# Thetis_RevF4_SCH.net
KiCad netlist of a schematic drawn in EAGLE
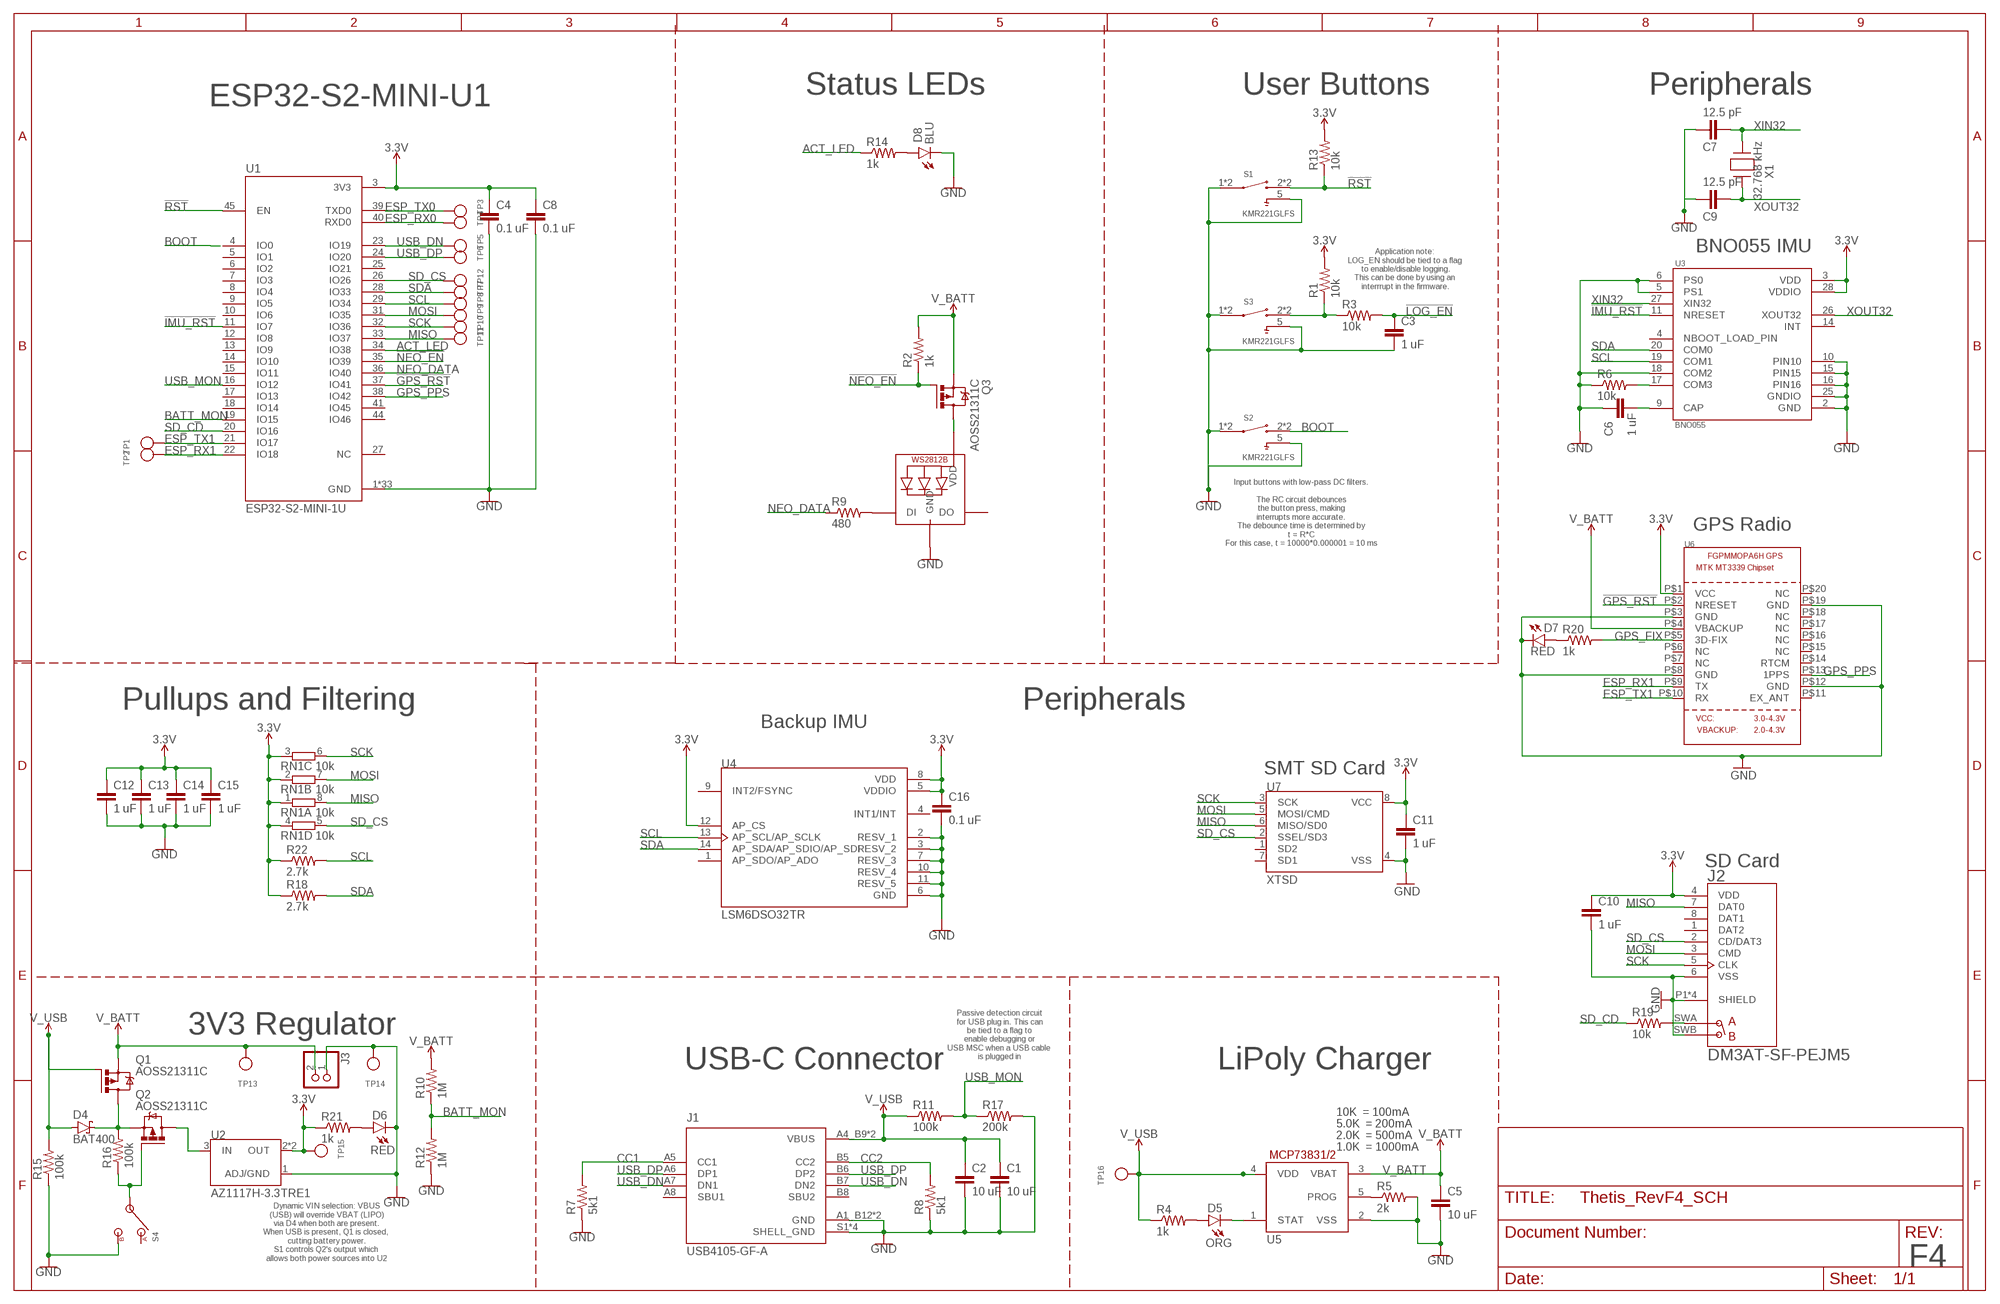
[diagram p0: schematic, sheet 1]

(export (version "E")
  (design (tool "Eeschema 10.0.6"))
  (components
    (comp (ref "C1")
      (value "10 uF")
      (footprint "eagle-import:C0603")
      (libsource (lib "eagle-import") (part "C-EUC0603"))
    )
    (comp (ref "C2")
      (value "10 uF")
      (footprint "eagle-import:C0603")
      (libsource (lib "eagle-import") (part "C-EUC0603"))
    )
    (comp (ref "C3")
      (value "1 uF")
      (footprint "eagle-import:C0603")
      (libsource (lib "eagle-import") (part "C-EUC0603"))
    )
    (comp (ref "C4")
      (value "0.1 uF")
      (footprint "eagle-import:C0603")
      (libsource (lib "eagle-import") (part "C-EUC0603"))
    )
    (comp (ref "C5")
      (value "10 uF")
      (footprint "eagle-import:C0603")
      (libsource (lib "eagle-import") (part "C-EUC0603"))
    )
    (comp (ref "C6")
      (value "1 uF")
      (footprint "eagle-import:C0603")
      (libsource (lib "eagle-import") (part "C-EUC0603"))
    )
    (comp (ref "C7")
      (value "12.5 pF")
      (footprint "eagle-import:C0603")
      (libsource (lib "eagle-import") (part "C-EUC0603"))
    )
    (comp (ref "C8")
      (value "0.1 uF")
      (footprint "eagle-import:C0603")
      (libsource (lib "eagle-import") (part "C-EUC0603"))
    )
    (comp (ref "C9")
      (value "12.5 pF")
      (footprint "eagle-import:C0603")
      (libsource (lib "eagle-import") (part "C-EUC0603"))
    )
    (comp (ref "C10")
      (value "1 uF")
      (footprint "eagle-import:C0603")
      (libsource (lib "eagle-import") (part "C-EUC0603"))
    )
    (comp (ref "C11")
      (value "1 uF")
      (footprint "eagle-import:C0603")
      (libsource (lib "eagle-import") (part "C-EUC0603"))
    )
    (comp (ref "C12")
      (value "1 uF")
      (footprint "eagle-import:C0603")
      (libsource (lib "eagle-import") (part "C-EUC0603"))
    )
    (comp (ref "C13")
      (value "1 uF")
      (footprint "eagle-import:C0603")
      (libsource (lib "eagle-import") (part "C-EUC0603"))
    )
    (comp (ref "C14")
      (value "1 uF")
      (footprint "eagle-import:C0603")
      (libsource (lib "eagle-import") (part "C-EUC0603"))
    )
    (comp (ref "C15")
      (value "1 uF")
      (footprint "eagle-import:C0603")
      (libsource (lib "eagle-import") (part "C-EUC0603"))
    )
    (comp (ref "C16")
      (value "0.1 uF")
      (footprint "eagle-import:C0603")
      (libsource (lib "eagle-import") (part "C-EUC0603"))
    )
    (comp (ref "D4")
      (value "BAT400")
      (footprint "eagle-import:SOT23")
      (libsource (lib "eagle-import") (part "BAS40"))
    )
    (comp (ref "D5")
      (value "ORG")
      (footprint "eagle-import:LEDC1608X65N")
      (libsource (lib "eagle-import") (part "CHIP-ROUND-G_0603"))
    )
    (comp (ref "D6")
      (value "RED")
      (footprint "eagle-import:LEDC1608X65N")
      (libsource (lib "eagle-import") (part "CHIP-ROUND-G_0603"))
    )
    (comp (ref "D7")
      (value "RED")
      (footprint "eagle-import:LEDC1608X35N")
      (libsource (lib "eagle-import") (part "CHIP-FLAT-Y_0603-0.35MM"))
    )
    (comp (ref "D8")
      (value "BLU")
      (footprint "eagle-import:LEDC1608X65N")
      (libsource (lib "eagle-import") (part "CHIP-ROUND-G_0603"))
    )
    (comp (ref "J1")
      (value "USB4105-GF-A")
      (footprint "eagle-import:GCT_USB4105-GF-A")
      (fields (field (name "MF") "GCT"))
      (libsource (lib "eagle-import") (part "USB4105-GF-A"))
    )
    (comp (ref "J2")
      (value "DM3AT-SF-PEJM5")
      (footprint "eagle-import:HRS_DM3AT-SF-PEJM5")
      (fields (field (name "MF") "Hirose"))
      (libsource (lib "eagle-import") (part "DM3AT-SF-PEJM5"))
    )
    (comp (ref "J3")
      (value "JST_2PIN")
      (footprint "eagle-import:JSTPH2")
      (libsource (lib "eagle-import") (part "JST_2PIN"))
    )
    (comp (ref "LED1")
      (value "WS2812B3535")
      (footprint "eagle-import:LED3535")
      (libsource (lib "eagle-import") (part "WS2812B3535"))
    )
    (comp (ref "Q1")
      (value "AOSS21311C")
      (footprint "eagle-import:SOT23")
      (fields (field (name "MANUFACTURER") "ON Semiconductor") (field (name "MPN") "BSS84"))
      (libsource (lib "eagle-import") (part "PMOSFET_BSS84"))
    )
    (comp (ref "Q2")
      (value "AOSS21311C")
      (footprint "eagle-import:SOT23")
      (fields (field (name "MANUFACTURER") "ON Semiconductor") (field (name "MPN") "BSS84"))
      (libsource (lib "eagle-import") (part "PMOSFET_BSS84"))
    )
    (comp (ref "Q3")
      (value "AOSS21311C")
      (footprint "eagle-import:SOT23")
      (fields (field (name "MANUFACTURER") "ON Semiconductor") (field (name "MPN") "BSS84"))
      (libsource (lib "eagle-import") (part "PMOSFET_BSS84"))
    )
    (comp (ref "R1")
      (value "10k")
      (footprint "eagle-import:R0603")
      (libsource (lib "eagle-import") (part "R-US_R0603"))
    )
    (comp (ref "R2")
      (value "1k")
      (footprint "eagle-import:R0603")
      (libsource (lib "eagle-import") (part "R-US_R0603"))
    )
    (comp (ref "R3")
      (value "10k")
      (footprint "eagle-import:R0603")
      (libsource (lib "eagle-import") (part "R-US_R0603"))
    )
    (comp (ref "R4")
      (value "1k")
      (footprint "eagle-import:R0603")
      (libsource (lib "eagle-import") (part "R-US_R0603"))
    )
    (comp (ref "R5")
      (value "2k")
      (footprint "eagle-import:R0603")
      (libsource (lib "eagle-import") (part "R-US_R0603"))
    )
    (comp (ref "R6")
      (value "10k")
      (footprint "eagle-import:R0603")
      (libsource (lib "eagle-import") (part "R-US_R0603"))
    )
    (comp (ref "R7")
      (value "5k1")
      (footprint "eagle-import:R0603")
      (libsource (lib "eagle-import") (part "R-US_R0603"))
    )
    (comp (ref "R8")
      (value "5k1")
      (footprint "eagle-import:R0603")
      (libsource (lib "eagle-import") (part "R-US_R0603"))
    )
    (comp (ref "R9")
      (value "480")
      (footprint "eagle-import:R0603")
      (libsource (lib "eagle-import") (part "R-US_R0603"))
    )
    (comp (ref "R10")
      (value "1M")
      (footprint "eagle-import:R0603")
      (libsource (lib "eagle-import") (part "R-US_R0603"))
    )
    (comp (ref "R11")
      (value "100k")
      (footprint "eagle-import:R0603")
      (libsource (lib "eagle-import") (part "R-US_R0603"))
    )
    (comp (ref "R12")
      (value "1M")
      (footprint "eagle-import:R0603")
      (libsource (lib "eagle-import") (part "R-US_R0603"))
    )
    (comp (ref "R13")
      (value "10k")
      (footprint "eagle-import:R0603")
      (libsource (lib "eagle-import") (part "R-US_R0603"))
    )
    (comp (ref "R14")
      (value "1k")
      (footprint "eagle-import:R0603")
      (libsource (lib "eagle-import") (part "R-US_R0603"))
    )
    (comp (ref "R15")
      (value "100k")
      (footprint "eagle-import:R0603")
      (libsource (lib "eagle-import") (part "R-US_R0603"))
    )
    (comp (ref "R16")
      (value "100k")
      (footprint "eagle-import:R0603")
      (libsource (lib "eagle-import") (part "R-US_R0603"))
    )
    (comp (ref "R17")
      (value "200k")
      (footprint "eagle-import:R0603")
      (libsource (lib "eagle-import") (part "R-US_R0603"))
    )
    (comp (ref "R18")
      (value "2.7k")
      (footprint "eagle-import:R0603")
      (libsource (lib "eagle-import") (part "R-US_R0603"))
    )
    (comp (ref "R19")
      (value "10k")
      (footprint "eagle-import:R0603")
      (libsource (lib "eagle-import") (part "R-US_R0603"))
    )
    (comp (ref "R20")
      (value "1k")
      (footprint "eagle-import:R0603")
      (libsource (lib "eagle-import") (part "R-US_R0603"))
    )
    (comp (ref "R21")
      (value "1k")
      (footprint "eagle-import:R0603")
      (libsource (lib "eagle-import") (part "R-US_R0603"))
    )
    (comp (ref "R22")
      (value "2.7k")
      (footprint "eagle-import:R0603")
      (libsource (lib "eagle-import") (part "R-US_R0603"))
    )
    (comp (ref "RN1")
      (value "10k")
      (footprint "eagle-import:EXBN8V")
      (libsource (lib "eagle-import") (part "4R-NEXBN8V"))
    )
    (comp (ref "S1")
      (value "KMR221GLFS")
      (footprint "eagle-import:SW_KMR221GLFS")
      (fields (field (name "MANUFACTURER") "CnK"))
      (libsource (lib "eagle-import") (part "KMR221GLFS"))
    )
    (comp (ref "S2")
      (value "KMR221GLFS")
      (footprint "eagle-import:SW_KMR221GLFS")
      (fields (field (name "MANUFACTURER") "CnK"))
      (libsource (lib "eagle-import") (part "KMR221GLFS"))
    )
    (comp (ref "S3")
      (value "KMR221GLFS")
      (footprint "eagle-import:SW_KMR221GLFS")
      (fields (field (name "MANUFACTURER") "CnK"))
      (libsource (lib "eagle-import") (part "KMR221GLFS"))
    )
    (comp (ref "S4")
      (value "CL-SB-12X")
      (footprint "eagle-import:CL-SB-12A")
      (libsource (lib "eagle-import") (part "CL-SB-12X"))
    )
    (comp (ref "TP1")
      (value "TESTPOINT1.5X2.0MM_NOCREAM")
      (footprint "eagle-import:PAD-1.5X2.0")
      (libsource (lib "eagle-import") (part "TESTPOINT1.5X2.0MM_NOCREAM"))
    )
    (comp (ref "TP2")
      (value "TESTPOINT1.5X2.0MM_NOCREAM")
      (footprint "eagle-import:PAD-1.5X2.0")
      (libsource (lib "eagle-import") (part "TESTPOINT1.5X2.0MM_NOCREAM"))
    )
    (comp (ref "TP3")
      (value "TESTPOINT1.5X2.0MM_NOCREAM")
      (footprint "eagle-import:PAD-1.5X2.0")
      (libsource (lib "eagle-import") (part "TESTPOINT1.5X2.0MM_NOCREAM"))
    )
    (comp (ref "TP4")
      (value "TESTPOINT1.5X2.0MM_NOCREAM")
      (footprint "eagle-import:PAD-1.5X2.0")
      (libsource (lib "eagle-import") (part "TESTPOINT1.5X2.0MM_NOCREAM"))
    )
    (comp (ref "TP5")
      (value "TESTPOINT1.5X2.0MM_NOCREAM")
      (footprint "eagle-import:PAD-1.5X2.0")
      (libsource (lib "eagle-import") (part "TESTPOINT1.5X2.0MM_NOCREAM"))
    )
    (comp (ref "TP6")
      (value "TESTPOINT1.5X2.0MM_NOCREAM")
      (footprint "eagle-import:PAD-1.5X2.0")
      (libsource (lib "eagle-import") (part "TESTPOINT1.5X2.0MM_NOCREAM"))
    )
    (comp (ref "TP7")
      (value "TESTPOINT1.5X2.0MM_NOCREAM")
      (footprint "eagle-import:PAD-1.5X2.0")
      (libsource (lib "eagle-import") (part "TESTPOINT1.5X2.0MM_NOCREAM"))
    )
    (comp (ref "TP8")
      (value "TESTPOINT1.5X2.0MM_NOCREAM")
      (footprint "eagle-import:PAD-1.5X2.0")
      (libsource (lib "eagle-import") (part "TESTPOINT1.5X2.0MM_NOCREAM"))
    )
    (comp (ref "TP9")
      (value "TESTPOINT1.5X2.0MM_NOCREAM")
      (footprint "eagle-import:PAD-1.5X2.0")
      (libsource (lib "eagle-import") (part "TESTPOINT1.5X2.0MM_NOCREAM"))
    )
    (comp (ref "TP10")
      (value "TESTPOINT1.5X2.0MM_NOCREAM")
      (footprint "eagle-import:PAD-1.5X2.0")
      (libsource (lib "eagle-import") (part "TESTPOINT1.5X2.0MM_NOCREAM"))
    )
    (comp (ref "TP11")
      (value "TESTPOINT1.5X2.0MM_NOCREAM")
      (footprint "eagle-import:PAD-1.5X2.0")
      (libsource (lib "eagle-import") (part "TESTPOINT1.5X2.0MM_NOCREAM"))
    )
    (comp (ref "TP12")
      (value "TESTPOINT1.5X2.0MM_NOCREAM")
      (footprint "eagle-import:PAD-1.5X2.0")
      (libsource (lib "eagle-import") (part "TESTPOINT1.5X2.0MM_NOCREAM"))
    )
    (comp (ref "TP13")
      (value "TESTPOINT1.5X2.0MM_NOCREAM")
      (footprint "eagle-import:PAD-1.5X2.0")
      (libsource (lib "eagle-import") (part "TESTPOINT1.5X2.0MM_NOCREAM"))
    )
    (comp (ref "TP14")
      (value "TESTPOINT1.5X2.0MM_NOCREAM")
      (footprint "eagle-import:PAD-1.5X2.0")
      (libsource (lib "eagle-import") (part "TESTPOINT1.5X2.0MM_NOCREAM"))
    )
    (comp (ref "TP15")
      (value "TESTPOINT1.5X2.0MM_NOCREAM")
      (footprint "eagle-import:PAD-1.5X2.0")
      (libsource (lib "eagle-import") (part "TESTPOINT1.5X2.0MM_NOCREAM"))
    )
    (comp (ref "TP16")
      (value "TESTPOINT1.5X2.0MM_NOCREAM")
      (footprint "eagle-import:PAD-1.5X2.0")
      (libsource (lib "eagle-import") (part "TESTPOINT1.5X2.0MM_NOCREAM"))
    )
    (comp (ref "U1")
      (value "ESP32-S2-MINI-1U")
      (footprint "eagle-import:XCVR_ESP32-S2-MINI-1U")
      (fields (field (name "MANUFACTURER") "Espressif Systems"))
      (libsource (lib "eagle-import") (part "ESP32-S2-MINI-1U"))
    )
    (comp (ref "U2")
      (value "AZ1117H-3.3TRE1")
      (footprint "eagle-import:SOT230P700X180-4N")
      (fields (field (name "MF") "Diodes Inc.") (field (name "MP") "AZ1117EH-5.0TRG1"))
      (libsource (lib "eagle-import") (part "AZ1117EH-5.0TRG1"))
    )
    (comp (ref "U3")
      (value "BNO055")
      (footprint "eagle-import:LGA28R50P4X10_380X520X100")
      (fields (field (name "MANUFACTURER") "BOSCH"))
      (libsource (lib "eagle-import") (part "BNO055"))
    )
    (comp (ref "U4")
      (value "LSM6DSO32TR")
      (footprint "eagle-import:PQFN50P300X250X97-14N")
      (fields (field (name "MANUFACTURER") "TDK Corporation"))
      (libsource (lib "eagle-import") (part "LSM6DSO32TR"))
    )
    (comp (ref "U5")
      (value "MCP73831/OT")
      (footprint "eagle-import:SOT23-5L")
      (libsource (lib "eagle-import") (part "MCP73831/OT"))
    )
    (comp (ref "U6")
      (value "GPS_FGPMMOPA6H")
      (footprint "eagle-import:FGPMMOPA6H")
      (libsource (lib "eagle-import") (part "GPS_FGPMMOPA6H"))
    )
    (comp (ref "U7")
      (value "XTSD")
      (footprint "eagle-import:LGA8_8X6")
      (libsource (lib "eagle-import") (part "SMT_SDCARD_8PIN"))
    )
    (comp (ref "X1")
      (value "32.768 kHz")
      (footprint "eagle-import:RT3215_RAL-L")
      (fields
        (field (name "MANUFACTURER_PART_NUMBER") "RT3215-32.768-12.5-TR")
        (field (name "COPYRIGHT") "Copyright (C) 2022 Ultra Librarian. All rights reserved.")
      )
      (libsource (lib "eagle-import") (part "RT3215-32.768-12.5-TRRT3215_RAL-L"))
    )
  )
  (nets
    (net (code "1") (name "/ACT_LED") (class "Default")
      (node (ref "R14") (pin "1") (pinfunction "1_1") (pintype "passive"))
      (node (ref "U1") (pin "34") (pinfunction "IO38_34") (pintype "bidirectional"))
    )
    (net (code "2") (name "/BATT_MON") (class "Default")
      (node (ref "R10") (pin "1") (pinfunction "1_1") (pintype "passive"))
      (node (ref "R12") (pin "2") (pinfunction "2_2") (pintype "passive"))
      (node (ref "U1") (pin "19") (pinfunction "IO15_19") (pintype "bidirectional"))
    )
    (net (code "3") (name "/BOOT") (class "Default")
      (node (ref "S2") (pin "2") (pinfunction "3_2") (pintype "passive"))
      (node (ref "S2") (pin "3") (pinfunction "3_3") (pintype "passive"))
      (node (ref "U1") (pin "4") (pinfunction "IO0_4") (pintype "bidirectional"))
    )
    (net (code "4") (name "/CC1") (class "Default")
      (node (ref "J1") (pin "A5") (pinfunction "CC1_A5") (pintype "bidirectional"))
      (node (ref "R7") (pin "2") (pinfunction "2_2") (pintype "passive"))
    )
    (net (code "5") (name "/CC2") (class "Default")
      (node (ref "J1") (pin "B5") (pinfunction "CC2_B5") (pintype "bidirectional"))
      (node (ref "R8") (pin "2") (pinfunction "2_2") (pintype "passive"))
    )
    (net (code "6") (name "/ESP_RX0") (class "Default")
      (node (ref "TP4") (pin "P$1") (pinfunction "P$1_P$1") (pintype "bidirectional"))
      (node (ref "U1") (pin "40") (pinfunction "RXD0_40") (pintype "bidirectional"))
    )
    (net (code "7") (name "/ESP_RX1") (class "Default")
      (node (ref "TP2") (pin "P$1") (pinfunction "P$1_P$1") (pintype "bidirectional"))
      (node (ref "U1") (pin "22") (pinfunction "IO18_22") (pintype "bidirectional"))
      (node (ref "U6") (pin "P$9") (pinfunction "TX_P$9") (pintype "bidirectional"))
    )
    (net (code "8") (name "/ESP_TX0") (class "Default")
      (node (ref "TP3") (pin "P$1") (pinfunction "P$1_P$1") (pintype "bidirectional"))
      (node (ref "U1") (pin "39") (pinfunction "TXD0_39") (pintype "bidirectional"))
    )
    (net (code "9") (name "/ESP_TX1") (class "Default")
      (node (ref "TP1") (pin "P$1") (pinfunction "P$1_P$1") (pintype "bidirectional"))
      (node (ref "U1") (pin "21") (pinfunction "IO17_21") (pintype "bidirectional"))
      (node (ref "U6") (pin "P$10") (pinfunction "RX_P$10") (pintype "bidirectional"))
    )
    (net (code "10") (name "/GPS_FIX") (class "Default")
      (node (ref "R20") (pin "2") (pinfunction "2_2") (pintype "passive"))
      (node (ref "U6") (pin "P$5") (pinfunction "3D-FIX_P$5") (pintype "bidirectional"))
    )
    (net (code "11") (name "/GPS_PPS") (class "Default")
      (node (ref "U1") (pin "38") (pinfunction "IO42_38") (pintype "bidirectional"))
      (node (ref "U6") (pin "P$13") (pinfunction "1PPS_P$13") (pintype "bidirectional"))
    )
    (net (code "12") (name "/MISO") (class "Default")
      (node (ref "J2") (pin "7") (pinfunction "DAT0_7") (pintype "bidirectional"))
      (node (ref "RN1") (pin "8") (pinfunction "2_8") (pintype "passive"))
      (node (ref "TP11") (pin "P$1") (pinfunction "P$1_P$1") (pintype "bidirectional"))
      (node (ref "U1") (pin "33") (pinfunction "IO37_33") (pintype "bidirectional"))
      (node (ref "U7") (pin "6") (pinfunction "MISO/SD0_6") (pintype "bidirectional"))
    )
    (net (code "13") (name "/MOSI") (class "Default")
      (node (ref "J2") (pin "3") (pinfunction "CMD_3") (pintype "bidirectional"))
      (node (ref "RN1") (pin "7") (pinfunction "2_7") (pintype "passive"))
      (node (ref "TP9") (pin "P$1") (pinfunction "P$1_P$1") (pintype "bidirectional"))
      (node (ref "U1") (pin "31") (pinfunction "IO35_31") (pintype "bidirectional"))
      (node (ref "U7") (pin "5") (pinfunction "MOSI/CMD_5") (pintype "bidirectional"))
    )
    (net (code "14") (name "/NEO_DATA") (class "Default")
      (node (ref "R9") (pin "1") (pinfunction "1_1") (pintype "passive"))
      (node (ref "U1") (pin "36") (pinfunction "IO40_36") (pintype "bidirectional"))
    )
    (net (code "15") (name "/SCK") (class "Default")
      (node (ref "J2") (pin "5") (pinfunction "CLK_5") (pintype "bidirectional"))
      (node (ref "RN1") (pin "6") (pinfunction "2_6") (pintype "passive"))
      (node (ref "TP10") (pin "P$1") (pinfunction "P$1_P$1") (pintype "bidirectional"))
      (node (ref "U1") (pin "32") (pinfunction "IO36_32") (pintype "bidirectional"))
      (node (ref "U7") (pin "3") (pinfunction "SCK_3") (pintype "input"))
    )
    (net (code "16") (name "/SCL") (class "Default")
      (node (ref "R22") (pin "2") (pinfunction "2_2") (pintype "passive"))
      (node (ref "TP8") (pin "P$1") (pinfunction "P$1_P$1") (pintype "bidirectional"))
      (node (ref "U1") (pin "29") (pinfunction "IO34_29") (pintype "bidirectional"))
      (node (ref "U3") (pin "19") (pinfunction "COM1_19") (pintype "bidirectional"))
      (node (ref "U4") (pin "13") (pinfunction "AP_SCL/AP_SCLK_13") (pintype "input"))
    )
    (net (code "17") (name "/SDA") (class "Default")
      (node (ref "R18") (pin "2") (pinfunction "2_2") (pintype "passive"))
      (node (ref "TP7") (pin "P$1") (pinfunction "P$1_P$1") (pintype "bidirectional"))
      (node (ref "U1") (pin "28") (pinfunction "IO33_28") (pintype "bidirectional"))
      (node (ref "U3") (pin "20") (pinfunction "COM0_20") (pintype "bidirectional"))
      (node (ref "U4") (pin "14") (pinfunction "AP_SDA/AP_SDIO/AP_SDI_14") (pintype "bidirectional"))
    )
    (net (code "18") (name "/SD_CD") (class "Default")
      (node (ref "R19") (pin "1") (pinfunction "1_1") (pintype "passive"))
      (node (ref "U1") (pin "20") (pinfunction "IO16_20") (pintype "bidirectional"))
    )
    (net (code "19") (name "/SD_CS") (class "Default")
      (node (ref "J2") (pin "2") (pinfunction "CD/DAT3_2") (pintype "bidirectional"))
      (node (ref "RN1") (pin "5") (pinfunction "2_5") (pintype "passive"))
      (node (ref "TP12") (pin "P$1") (pinfunction "P$1_P$1") (pintype "bidirectional"))
      (node (ref "U1") (pin "26") (pinfunction "IO26_26") (pintype "bidirectional"))
      (node (ref "U7") (pin "2") (pinfunction "SSEL/SD3_2") (pintype "bidirectional"))
    )
    (net (code "20") (name "/USB_DN") (class "Default")
      (node (ref "J1") (pin "A7") (pinfunction "DN1_A7") (pintype "bidirectional"))
      (node (ref "J1") (pin "B7") (pinfunction "DN2_B7") (pintype "bidirectional"))
      (node (ref "TP5") (pin "P$1") (pinfunction "P$1_P$1") (pintype "bidirectional"))
      (node (ref "U1") (pin "23") (pinfunction "IO19_23") (pintype "bidirectional"))
    )
    (net (code "21") (name "/USB_DP") (class "Default")
      (node (ref "J1") (pin "A6") (pinfunction "DP1_A6") (pintype "bidirectional"))
      (node (ref "J1") (pin "B6") (pinfunction "DP2_B6") (pintype "bidirectional"))
      (node (ref "TP6") (pin "P$1") (pinfunction "P$1_P$1") (pintype "bidirectional"))
      (node (ref "U1") (pin "24") (pinfunction "IO20_24") (pintype "bidirectional"))
    )
    (net (code "22") (name "/USB_MON") (class "Default")
      (node (ref "R11") (pin "2") (pinfunction "2_2") (pintype "passive"))
      (node (ref "R17") (pin "1") (pinfunction "1_1") (pintype "passive"))
      (node (ref "U1") (pin "16") (pinfunction "IO12_16") (pintype "bidirectional"))
    )
    (net (code "23") (name "/XIN32") (class "Default")
      (node (ref "C7") (pin "2") (pinfunction "2_2") (pintype "passive"))
      (node (ref "U3") (pin "27") (pinfunction "XIN32_27") (pintype "input"))
      (node (ref "X1") (pin "1") (pinfunction "1_1") (pintype "passive"))
    )
    (net (code "24") (name "/XOUT32") (class "Default")
      (node (ref "C9") (pin "2") (pinfunction "2_2") (pintype "passive"))
      (node (ref "U3") (pin "26") (pinfunction "XOUT32_26") (pintype "output"))
      (node (ref "X1") (pin "2") (pinfunction "2_2") (pintype "passive"))
    )
    (net (code "25") (name "/~{GPS_RST}") (class "Default")
      (node (ref "U1") (pin "37") (pinfunction "IO41_37") (pintype "bidirectional"))
      (node (ref "U6") (pin "P$2") (pinfunction "NRESET_P$2") (pintype "bidirectional"))
    )
    (net (code "26") (name "/~{IMU_RST}") (class "Default")
      (node (ref "U1") (pin "11") (pinfunction "IO7_11") (pintype "bidirectional"))
      (node (ref "U3") (pin "11") (pinfunction "NRESET_11") (pintype "input"))
    )
    (net (code "27") (name "/~{LOG_EN}") (class "Default")
      (node (ref "C3") (pin "1") (pinfunction "1_1") (pintype "passive"))
      (node (ref "R3") (pin "2") (pinfunction "2_2") (pintype "passive"))
    )
    (net (code "28") (name "/~{NEO_EN}") (class "Default")
      (node (ref "Q3") (pin "1") (pinfunction "G_1") (pintype "passive"))
      (node (ref "R2") (pin "1") (pinfunction "1_1") (pintype "passive"))
      (node (ref "U1") (pin "35") (pinfunction "IO39_35") (pintype "bidirectional"))
    )
    (net (code "29") (name "/~{RST}") (class "Default")
      (node (ref "R13") (pin "1") (pinfunction "1_1") (pintype "passive"))
      (node (ref "S1") (pin "2") (pinfunction "3_2") (pintype "passive"))
      (node (ref "S1") (pin "3") (pinfunction "3_3") (pintype "passive"))
      (node (ref "U1") (pin "45") (pinfunction "EN_45") (pintype "input"))
    )
    (net (code "30") (name "3.3V") (class "Default")
      (node (ref "C10") (pin "1") (pinfunction "1_1") (pintype "passive"))
      (node (ref "C11") (pin "1") (pinfunction "1_1") (pintype "passive"))
      (node (ref "C12") (pin "1") (pinfunction "1_1") (pintype "passive"))
      (node (ref "C13") (pin "1") (pinfunction "1_1") (pintype "passive"))
      (node (ref "C14") (pin "1") (pinfunction "1_1") (pintype "passive"))
      (node (ref "C15") (pin "1") (pinfunction "1_1") (pintype "passive"))
      (node (ref "C16") (pin "1") (pinfunction "1_1") (pintype "passive"))
      (node (ref "C4") (pin "1") (pinfunction "1_1") (pintype "passive"))
      (node (ref "C8") (pin "1") (pinfunction "1_1") (pintype "passive"))
      (node (ref "J2") (pin "4") (pinfunction "VDD_4") (pintype "power_in"))
      (node (ref "R1") (pin "2") (pinfunction "2_2") (pintype "passive"))
      (node (ref "R13") (pin "2") (pinfunction "2_2") (pintype "passive"))
      (node (ref "R18") (pin "1") (pinfunction "1_1") (pintype "passive"))
      (node (ref "R21") (pin "1") (pinfunction "1_1") (pintype "passive"))
      (node (ref "R22") (pin "1") (pinfunction "1_1") (pintype "passive"))
      (node (ref "RN1") (pin "1") (pinfunction "1_1") (pintype "passive"))
      (node (ref "RN1") (pin "2") (pinfunction "1_2") (pintype "passive"))
      (node (ref "RN1") (pin "3") (pinfunction "1_3") (pintype "passive"))
      (node (ref "RN1") (pin "4") (pinfunction "1_4") (pintype "passive"))
      (node (ref "TP15") (pin "P$1") (pinfunction "P$1_P$1") (pintype "bidirectional"))
      (node (ref "U1") (pin "3") (pinfunction "3V3_3") (pintype "power_in"))
      (node (ref "U2") (pin "2") (pinfunction "OUT_2") (pintype "output"))
      (node (ref "U2") (pin "4") (pinfunction "OUT_4") (pintype "output"))
      (node (ref "U3") (pin "28") (pinfunction "VDDIO_28") (pintype "power_in"))
      (node (ref "U3") (pin "3") (pinfunction "VDD_3") (pintype "power_in"))
      (node (ref "U4") (pin "12") (pinfunction "AP_CS_12") (pintype "input"))
      (node (ref "U4") (pin "5") (pinfunction "VDDIO_5") (pintype "power_in"))
      (node (ref "U4") (pin "8") (pinfunction "VDD_8") (pintype "power_in"))
      (node (ref "U6") (pin "P$1") (pinfunction "VCC_P$1") (pintype "bidirectional"))
      (node (ref "U7") (pin "8") (pinfunction "VCC_8") (pintype "power_in"))
    )
    (net (code "31") (name "GND") (class "Default")
      (node (ref "C1") (pin "2") (pinfunction "2_2") (pintype "passive"))
      (node (ref "C10") (pin "2") (pinfunction "2_2") (pintype "passive"))
      (node (ref "C11") (pin "2") (pinfunction "2_2") (pintype "passive"))
      (node (ref "C12") (pin "2") (pinfunction "2_2") (pintype "passive"))
      (node (ref "C13") (pin "2") (pinfunction "2_2") (pintype "passive"))
      (node (ref "C14") (pin "2") (pinfunction "2_2") (pintype "passive"))
      (node (ref "C15") (pin "2") (pinfunction "2_2") (pintype "passive"))
      (node (ref "C16") (pin "2") (pinfunction "2_2") (pintype "passive"))
      (node (ref "C2") (pin "2") (pinfunction "2_2") (pintype "passive"))
      (node (ref "C3") (pin "2") (pinfunction "2_2") (pintype "passive"))
      (node (ref "C4") (pin "2") (pinfunction "2_2") (pintype "passive"))
      (node (ref "C5") (pin "2") (pinfunction "2_2") (pintype "passive"))
      (node (ref "C6") (pin "1") (pinfunction "1_1") (pintype "passive"))
      (node (ref "C7") (pin "1") (pinfunction "1_1") (pintype "passive"))
      (node (ref "C8") (pin "2") (pinfunction "2_2") (pintype "passive"))
      (node (ref "C9") (pin "1") (pinfunction "1_1") (pintype "passive"))
      (node (ref "D6") (pin "C") (pinfunction "C_C") (pintype "passive"))
      (node (ref "D7") (pin "C") (pinfunction "C_C") (pintype "passive"))
      (node (ref "D8") (pin "C") (pinfunction "C_C") (pintype "passive"))
      (node (ref "J1") (pin "A1_B12") (pinfunction "GND_A1_B12") (pintype "power_in"))
      (node (ref "J1") (pin "B1_A12") (pinfunction "GND_B1_A12") (pintype "power_in"))
      (node (ref "J1") (pin "S1") (pinfunction "SHELL_GND_S1") (pintype "power_in"))
      (node (ref "J1") (pin "S2") (pinfunction "SHELL_GND_S2") (pintype "power_in"))
      (node (ref "J1") (pin "S3") (pinfunction "SHELL_GND_S3") (pintype "power_in"))
      (node (ref "J1") (pin "S4") (pinfunction "SHELL_GND_S4") (pintype "power_in"))
      (node (ref "J2") (pin "6") (pinfunction "VSS_6") (pintype "power_in"))
      (node (ref "J2") (pin "P1") (pinfunction "SHIELD_P1") (pintype "passive"))
      (node (ref "J2") (pin "P2") (pinfunction "SHIELD_P2") (pintype "passive"))
      (node (ref "J2") (pin "P3") (pinfunction "SHIELD_P3") (pintype "passive"))
      (node (ref "J2") (pin "P4") (pinfunction "SHIELD_P4") (pintype "passive"))
      (node (ref "J2") (pin "SWB") (pinfunction "B_SWB") (pintype "bidirectional"))
      (node (ref "J3") (pin "1") (pinfunction "1_1") (pintype "passive"))
      (node (ref "LED1") (pin "4") (pinfunction "GND_4") (pintype "power_in"))
      (node (ref "R12") (pin "1") (pinfunction "1_1") (pintype "passive"))
      (node (ref "R15") (pin "1") (pinfunction "1_1") (pintype "passive"))
      (node (ref "R17") (pin "2") (pinfunction "2_2") (pintype "passive"))
      (node (ref "R5") (pin "2") (pinfunction "2_2") (pintype "passive"))
      (node (ref "R6") (pin "1") (pinfunction "1_1") (pintype "passive"))
      (node (ref "R7") (pin "1") (pinfunction "1_1") (pintype "passive"))
      (node (ref "R8") (pin "1") (pinfunction "1_1") (pintype "passive"))
      (node (ref "S1") (pin "1") (pinfunction "1_1") (pintype "passive"))
      (node (ref "S1") (pin "4") (pinfunction "1_4") (pintype "passive"))
      (node (ref "S1") (pin "5") (pinfunction "5_5") (pintype "passive"))
      (node (ref "S2") (pin "1") (pinfunction "1_1") (pintype "passive"))
      (node (ref "S2") (pin "4") (pinfunction "1_4") (pintype "passive"))
      (node (ref "S2") (pin "5") (pinfunction "5_5") (pintype "passive"))
      (node (ref "S3") (pin "1") (pinfunction "1_1") (pintype "passive"))
      (node (ref "S3") (pin "4") (pinfunction "1_4") (pintype "passive"))
      (node (ref "S3") (pin "5") (pinfunction "5_5") (pintype "passive"))
      (node (ref "S4") (pin "3") (pinfunction "3_3") (pintype "bidirectional"))
      (node (ref "TP14") (pin "P$1") (pinfunction "P$1_P$1") (pintype "bidirectional"))
      (node (ref "U1") (pin "1") (pinfunction "GND_1") (pintype "power_in"))
      (node (ref "U1") (pin "2") (pinfunction "GND_2") (pintype "power_in"))
      (node (ref "U1") (pin "30") (pinfunction "GND_30") (pintype "power_in"))
      (node (ref "U1") (pin "42") (pinfunction "GND_42") (pintype "power_in"))
      (node (ref "U1") (pin "43") (pinfunction "GND_43") (pintype "power_in"))
      (node (ref "U1") (pin "46") (pinfunction "GND_46") (pintype "power_in"))
      (node (ref "U1") (pin "47") (pinfunction "GND_47") (pintype "power_in"))
      (node (ref "U1") (pin "48") (pinfunction "GND_48") (pintype "power_in"))
      (node (ref "U1") (pin "49") (pinfunction "GND_49") (pintype "power_in"))
      (node (ref "U1") (pin "50") (pinfunction "GND_50") (pintype "power_in"))
      (node (ref "U1") (pin "51") (pinfunction "GND_51") (pintype "power_in"))
      (node (ref "U1") (pin "52") (pinfunction "GND_52") (pintype "power_in"))
      (node (ref "U1") (pin "53") (pinfunction "GND_53") (pintype "power_in"))
      (node (ref "U1") (pin "54") (pinfunction "GND_54") (pintype "power_in"))
      (node (ref "U1") (pin "55") (pinfunction "GND_55") (pintype "power_in"))
      (node (ref "U1") (pin "56") (pinfunction "GND_56") (pintype "power_in"))
      (node (ref "U1") (pin "57") (pinfunction "GND_57") (pintype "power_in"))
      (node (ref "U1") (pin "58") (pinfunction "GND_58") (pintype "power_in"))
      (node (ref "U1") (pin "59") (pinfunction "GND_59") (pintype "power_in"))
      (node (ref "U1") (pin "60") (pinfunction "GND_60") (pintype "power_in"))
      (node (ref "U1") (pin "61_0") (pinfunction "GND_61_0") (pintype "power_in"))
      (node (ref "U1") (pin "61_1") (pinfunction "GND_61_1") (pintype "power_in"))
      (node (ref "U1") (pin "61_2") (pinfunction "GND_61_2") (pintype "power_in"))
      (node (ref "U1") (pin "61_3") (pinfunction "GND_61_3") (pintype "power_in"))
      (node (ref "U1") (pin "61_4") (pinfunction "GND_61_4") (pintype "power_in"))
      (node (ref "U1") (pin "61_5") (pinfunction "GND_61_5") (pintype "power_in"))
      (node (ref "U1") (pin "61_6") (pinfunction "GND_61_6") (pintype "power_in"))
      (node (ref "U1") (pin "61_7") (pinfunction "GND_61_7") (pintype "power_in"))
      (node (ref "U1") (pin "61_8") (pinfunction "GND_61_8") (pintype "power_in"))
      (node (ref "U1") (pin "62") (pinfunction "GND_62") (pintype "power_in"))
      (node (ref "U1") (pin "63") (pinfunction "GND_63") (pintype "power_in"))
      (node (ref "U1") (pin "64") (pinfunction "GND_64") (pintype "power_in"))
      (node (ref "U1") (pin "65") (pinfunction "GND_65") (pintype "power_in"))
      (node (ref "U2") (pin "1") (pinfunction "ADJ/GND_1") (pintype "power_in"))
      (node (ref "U3") (pin "10") (pinfunction "PIN10_10") (pintype "power_in"))
      (node (ref "U3") (pin "15") (pinfunction "PIN15_15") (pintype "power_in"))
      (node (ref "U3") (pin "16") (pinfunction "PIN16_16") (pintype "power_in"))
      (node (ref "U3") (pin "18") (pinfunction "COM2_18") (pintype "bidirectional"))
      (node (ref "U3") (pin "2") (pinfunction "GND_2") (pintype "power_in"))
      (node (ref "U3") (pin "25") (pinfunction "GNDIO_25") (pintype "power_in"))
      (node (ref "U3") (pin "5") (pinfunction "PS1_5") (pintype "input"))
      (node (ref "U3") (pin "6") (pinfunction "PS0_6") (pintype "input"))
      (node (ref "U4") (pin "10") (pinfunction "RESV_4_10") (pintype "bidirectional"))
      (node (ref "U4") (pin "11") (pinfunction "RESV_5_11") (pintype "bidirectional"))
      (node (ref "U4") (pin "2") (pinfunction "RESV_1_2") (pintype "bidirectional"))
      (node (ref "U4") (pin "3") (pinfunction "RESV_2_3") (pintype "bidirectional"))
      (node (ref "U4") (pin "6") (pinfunction "GND_6") (pintype "power_in"))
      (node (ref "U4") (pin "7") (pinfunction "RESV_3_7") (pintype "bidirectional"))
      (node (ref "U5") (pin "2") (pinfunction "VSS_2") (pintype "power_in"))
      (node (ref "U6") (pin "P$12") (pinfunction "GND_P$12") (pintype "bidirectional"))
      (node (ref "U6") (pin "P$19") (pinfunction "GND_P$19") (pintype "bidirectional"))
      (node (ref "U6") (pin "P$3") (pinfunction "GND_P$3") (pintype "bidirectional"))
      (node (ref "U6") (pin "P$8") (pinfunction "GND_P$8") (pintype "bidirectional"))
      (node (ref "U7") (pin "4") (pinfunction "VSS_4") (pintype "power_in"))
    )
    (net (code "32") (name "Net-(D4-C)") (class "Default")
      (node (ref "D4") (pin "3") (pinfunction "C_3") (pintype "passive"))
      (node (ref "Q1") (pin "3") (pinfunction "D_3") (pintype "passive"))
      (node (ref "Q2") (pin "2") (pinfunction "S_2") (pintype "passive"))
      (node (ref "R16") (pin "2") (pinfunction "2_2") (pintype "passive"))
    )
    (net (code "33") (name "Net-(D5-PadA)") (class "Default")
      (node (ref "D5") (pin "A") (pinfunction "A_A") (pintype "passive"))
      (node (ref "R4") (pin "2") (pinfunction "2_2") (pintype "passive"))
    )
    (net (code "34") (name "Net-(D6-PadA)") (class "Default")
      (node (ref "D6") (pin "A") (pinfunction "A_A") (pintype "passive"))
      (node (ref "R21") (pin "2") (pinfunction "2_2") (pintype "passive"))
    )
    (net (code "35") (name "Net-(D7-PadA)") (class "Default")
      (node (ref "D7") (pin "A") (pinfunction "A_A") (pintype "passive"))
      (node (ref "R20") (pin "1") (pinfunction "1_1") (pintype "passive"))
    )
    (net (code "36") (name "Net-(D8-PadA)") (class "Default")
      (node (ref "D8") (pin "A") (pinfunction "A_A") (pintype "passive"))
      (node (ref "R14") (pin "2") (pinfunction "2_2") (pintype "passive"))
    )
    (net (code "37") (name "Net-(J2-A)") (class "Default")
      (node (ref "J2") (pin "SWA") (pinfunction "A_SWA") (pintype "bidirectional"))
      (node (ref "R19") (pin "2") (pinfunction "2_2") (pintype "passive"))
    )
    (net (code "38") (name "Net-(LED1-DI)") (class "Default")
      (node (ref "LED1") (pin "1") (pinfunction "DI_1") (pintype "input"))
      (node (ref "R9") (pin "2") (pinfunction "2_2") (pintype "passive"))
    )
    (net (code "39") (name "Net-(LED1-VDD)") (class "Default")
      (node (ref "LED1") (pin "2") (pinfunction "VDD_2") (pintype "power_in"))
      (node (ref "Q3") (pin "3") (pinfunction "D_3") (pintype "passive"))
    )
    (net (code "40") (name "Net-(Q2-D)") (class "Default")
      (node (ref "Q2") (pin "3") (pinfunction "D_3") (pintype "passive"))
      (node (ref "U2") (pin "3") (pinfunction "IN_3") (pintype "input"))
    )
    (net (code "41") (name "Net-(Q2-G)") (class "Default")
      (node (ref "Q2") (pin "1") (pinfunction "G_1") (pintype "passive"))
      (node (ref "R16") (pin "1") (pinfunction "1_1") (pintype "passive"))
      (node (ref "S4") (pin "2") (pinfunction "2_2") (pintype "bidirectional"))
    )
    (net (code "42") (name "Net-(R1-Pad1)") (class "Default")
      (node (ref "R1") (pin "1") (pinfunction "1_1") (pintype "passive"))
      (node (ref "R3") (pin "1") (pinfunction "1_1") (pintype "passive"))
      (node (ref "S3") (pin "2") (pinfunction "3_2") (pintype "passive"))
      (node (ref "S3") (pin "3") (pinfunction "3_3") (pintype "passive"))
    )
    (net (code "43") (name "Net-(U3-CAP)") (class "Default")
      (node (ref "C6") (pin "2") (pinfunction "2_2") (pintype "passive"))
      (node (ref "U3") (pin "9") (pinfunction "CAP_9") (pintype "passive"))
    )
    (net (code "44") (name "Net-(U3-COM3)") (class "Default")
      (node (ref "R6") (pin "2") (pinfunction "2_2") (pintype "passive"))
      (node (ref "U3") (pin "17") (pinfunction "COM3_17") (pintype "bidirectional"))
    )
    (net (code "45") (name "Net-(U5-PROG)") (class "Default")
      (node (ref "R5") (pin "1") (pinfunction "1_1") (pintype "passive"))
      (node (ref "U5") (pin "5") (pinfunction "PROG_5") (pintype "input"))
    )
    (net (code "46") (name "Net-(U5-STAT)") (class "Default")
      (node (ref "D5") (pin "C") (pinfunction "C_C") (pintype "passive"))
      (node (ref "U5") (pin "1") (pinfunction "STAT_1") (pintype "output"))
    )
    (net (code "47") (name "V_BATT") (class "Default")
      (node (ref "C5") (pin "1") (pinfunction "1_1") (pintype "passive"))
      (node (ref "J3") (pin "2") (pinfunction "2_2") (pintype "passive"))
      (node (ref "Q1") (pin "2") (pinfunction "S_2") (pintype "passive"))
      (node (ref "Q3") (pin "2") (pinfunction "S_2") (pintype "passive"))
      (node (ref "R10") (pin "2") (pinfunction "2_2") (pintype "passive"))
      (node (ref "R2") (pin "2") (pinfunction "2_2") (pintype "passive"))
      (node (ref "TP13") (pin "P$1") (pinfunction "P$1_P$1") (pintype "bidirectional"))
      (node (ref "U5") (pin "3") (pinfunction "VBAT_3") (pintype "bidirectional"))
      (node (ref "U6") (pin "P$4") (pinfunction "VBACKUP_P$4") (pintype "bidirectional"))
    )
    (net (code "48") (name "V_USB") (class "Default")
      (node (ref "C1") (pin "1") (pinfunction "1_1") (pintype "passive"))
      (node (ref "C2") (pin "1") (pinfunction "1_1") (pintype "passive"))
      (node (ref "D4") (pin "1") (pinfunction "A_1") (pintype "passive"))
      (node (ref "J1") (pin "A4_B9") (pinfunction "VBUS_A4_B9") (pintype "power_in"))
      (node (ref "J1") (pin "B4_A9") (pinfunction "VBUS_B4_A9") (pintype "power_in"))
      (node (ref "Q1") (pin "1") (pinfunction "G_1") (pintype "passive"))
      (node (ref "R11") (pin "1") (pinfunction "1_1") (pintype "passive"))
      (node (ref "R15") (pin "2") (pinfunction "2_2") (pintype "passive"))
      (node (ref "R4") (pin "1") (pinfunction "1_1") (pintype "passive"))
      (node (ref "TP16") (pin "P$1") (pinfunction "P$1_P$1") (pintype "bidirectional"))
      (node (ref "U5") (pin "4") (pinfunction "VDD_4") (pintype "power_in"))
    )
    (net (code "49") (name "unconnected-(J1-SBU1-PadA8)") (class "Default")
      (node (ref "J1") (pin "A8") (pinfunction "SBU1_A8") (pintype "bidirectional"))
    )
    (net (code "50") (name "unconnected-(J1-SBU2-PadB8)") (class "Default")
      (node (ref "J1") (pin "B8") (pinfunction "SBU2_B8") (pintype "bidirectional"))
    )
    (net (code "51") (name "unconnected-(J2-DAT1-Pad8)") (class "Default")
      (node (ref "J2") (pin "8") (pinfunction "DAT1_8") (pintype "bidirectional"))
    )
    (net (code "52") (name "unconnected-(J2-DAT2-Pad1)") (class "Default")
      (node (ref "J2") (pin "1") (pinfunction "DAT2_1") (pintype "bidirectional"))
    )
    (net (code "53") (name "unconnected-(LED1-DO-Pad3)") (class "Default")
      (node (ref "LED1") (pin "3") (pinfunction "DO_3") (pintype "output"))
    )
    (net (code "54") (name "unconnected-(S4-Pad1)") (class "Default")
      (node (ref "S4") (pin "1") (pinfunction "1_1") (pintype "bidirectional"))
    )
    (net (code "55") (name "unconnected-(U1-IO1-Pad5)") (class "Default")
      (node (ref "U1") (pin "5") (pinfunction "IO1_5") (pintype "bidirectional"))
    )
    (net (code "56") (name "unconnected-(U1-IO2-Pad6)") (class "Default")
      (node (ref "U1") (pin "6") (pinfunction "IO2_6") (pintype "bidirectional"))
    )
    (net (code "57") (name "unconnected-(U1-IO3-Pad7)") (class "Default")
      (node (ref "U1") (pin "7") (pinfunction "IO3_7") (pintype "bidirectional"))
    )
    (net (code "58") (name "unconnected-(U1-IO4-Pad8)") (class "Default")
      (node (ref "U1") (pin "8") (pinfunction "IO4_8") (pintype "bidirectional"))
    )
    (net (code "59") (name "unconnected-(U1-IO5-Pad9)") (class "Default")
      (node (ref "U1") (pin "9") (pinfunction "IO5_9") (pintype "bidirectional"))
    )
    (net (code "60") (name "unconnected-(U1-IO6-Pad10)") (class "Default")
      (node (ref "U1") (pin "10") (pinfunction "IO6_10") (pintype "bidirectional"))
    )
    (net (code "61") (name "unconnected-(U1-IO8-Pad12)") (class "Default")
      (node (ref "U1") (pin "12") (pinfunction "IO8_12") (pintype "bidirectional"))
    )
    (net (code "62") (name "unconnected-(U1-IO9-Pad13)") (class "Default")
      (node (ref "U1") (pin "13") (pinfunction "IO9_13") (pintype "bidirectional"))
    )
    (net (code "63") (name "unconnected-(U1-IO10-Pad14)") (class "Default")
      (node (ref "U1") (pin "14") (pinfunction "IO10_14") (pintype "bidirectional"))
    )
    (net (code "64") (name "unconnected-(U1-IO11-Pad15)") (class "Default")
      (node (ref "U1") (pin "15") (pinfunction "IO11_15") (pintype "bidirectional"))
    )
    (net (code "65") (name "unconnected-(U1-IO13-Pad17)") (class "Default")
      (node (ref "U1") (pin "17") (pinfunction "IO13_17") (pintype "bidirectional"))
    )
    (net (code "66") (name "unconnected-(U1-IO14-Pad18)") (class "Default")
      (node (ref "U1") (pin "18") (pinfunction "IO14_18") (pintype "bidirectional"))
    )
    (net (code "67") (name "unconnected-(U1-IO21-Pad25)") (class "Default")
      (node (ref "U1") (pin "25") (pinfunction "IO21_25") (pintype "bidirectional"))
    )
    (net (code "68") (name "unconnected-(U1-IO45-Pad41)") (class "Default")
      (node (ref "U1") (pin "41") (pinfunction "IO45_41") (pintype "bidirectional"))
    )
    (net (code "69") (name "unconnected-(U1-IO46-Pad44)") (class "Default")
      (node (ref "U1") (pin "44") (pinfunction "IO46_44") (pintype "input"))
    )
    (net (code "70") (name "unconnected-(U1-NC-Pad27)") (class "Default")
      (node (ref "U1") (pin "27") (pinfunction "NC_27") (pintype "no_connect"))
    )
    (net (code "71") (name "unconnected-(U3-INT-Pad14)") (class "Default")
      (node (ref "U3") (pin "14") (pinfunction "INT_14") (pintype "output"))
    )
    (net (code "72") (name "unconnected-(U3-NBOOT_LOAD_PIN-Pad4)") (class "Default")
      (node (ref "U3") (pin "4") (pinfunction "NBOOT_LOAD_PIN_4") (pintype "bidirectional"))
    )
    (net (code "73") (name "unconnected-(U4-AP_SDO{slash}AP_ADO-Pad1)") (class "Default")
      (node (ref "U4") (pin "1") (pinfunction "AP_SDO/AP_ADO_1") (pintype "output"))
    )
    (net (code "74") (name "unconnected-(U4-INT1{slash}INT-Pad4)") (class "Default")
      (node (ref "U4") (pin "4") (pinfunction "INT1/INT_4") (pintype "output"))
    )
    (net (code "75") (name "unconnected-(U4-INT2{slash}FSYNC-Pad9)") (class "Default")
      (node (ref "U4") (pin "9") (pinfunction "INT2/FSYNC_9") (pintype "bidirectional"))
    )
    (net (code "76") (name "unconnected-(U6-EX_ANT-PadP$11)") (class "Default")
      (node (ref "U6") (pin "P$11") (pinfunction "EX_ANT_P$11") (pintype "bidirectional"))
    )
    (net (code "77") (name "unconnected-(U6-NC-PadP$6)") (class "Default")
      (node (ref "U6") (pin "P$6") (pinfunction "NC_P$6") (pintype "bidirectional"))
    )
    (net (code "78") (name "unconnected-(U6-NC-PadP$7)") (class "Default")
      (node (ref "U6") (pin "P$7") (pinfunction "NC_P$7") (pintype "bidirectional"))
    )
    (net (code "79") (name "unconnected-(U6-NC-PadP$15)") (class "Default")
      (node (ref "U6") (pin "P$15") (pinfunction "NC_P$15") (pintype "bidirectional"))
    )
    (net (code "80") (name "unconnected-(U6-NC-PadP$16)") (class "Default")
      (node (ref "U6") (pin "P$16") (pinfunction "NC_P$16") (pintype "bidirectional"))
    )
    (net (code "81") (name "unconnected-(U6-NC-PadP$17)") (class "Default")
      (node (ref "U6") (pin "P$17") (pinfunction "NC_P$17") (pintype "bidirectional"))
    )
    (net (code "82") (name "unconnected-(U6-NC-PadP$18)") (class "Default")
      (node (ref "U6") (pin "P$18") (pinfunction "NC_P$18") (pintype "bidirectional"))
    )
    (net (code "83") (name "unconnected-(U6-NC-PadP$20)") (class "Default")
      (node (ref "U6") (pin "P$20") (pinfunction "NC_P$20") (pintype "bidirectional"))
    )
    (net (code "84") (name "unconnected-(U6-RTCM-PadP$14)") (class "Default")
      (node (ref "U6") (pin "P$14") (pinfunction "RTCM_P$14") (pintype "bidirectional"))
    )
    (net (code "85") (name "unconnected-(U7-SD1-Pad7)") (class "Default")
      (node (ref "U7") (pin "7") (pinfunction "SD1_7") (pintype "bidirectional"))
    )
    (net (code "86") (name "unconnected-(U7-SD2-Pad1)") (class "Default")
      (node (ref "U7") (pin "1") (pinfunction "SD2_1") (pintype "bidirectional"))
    )
  )
)
